# uart-cut.net
KiCad netlist of a schematic drawn in Altium Designer
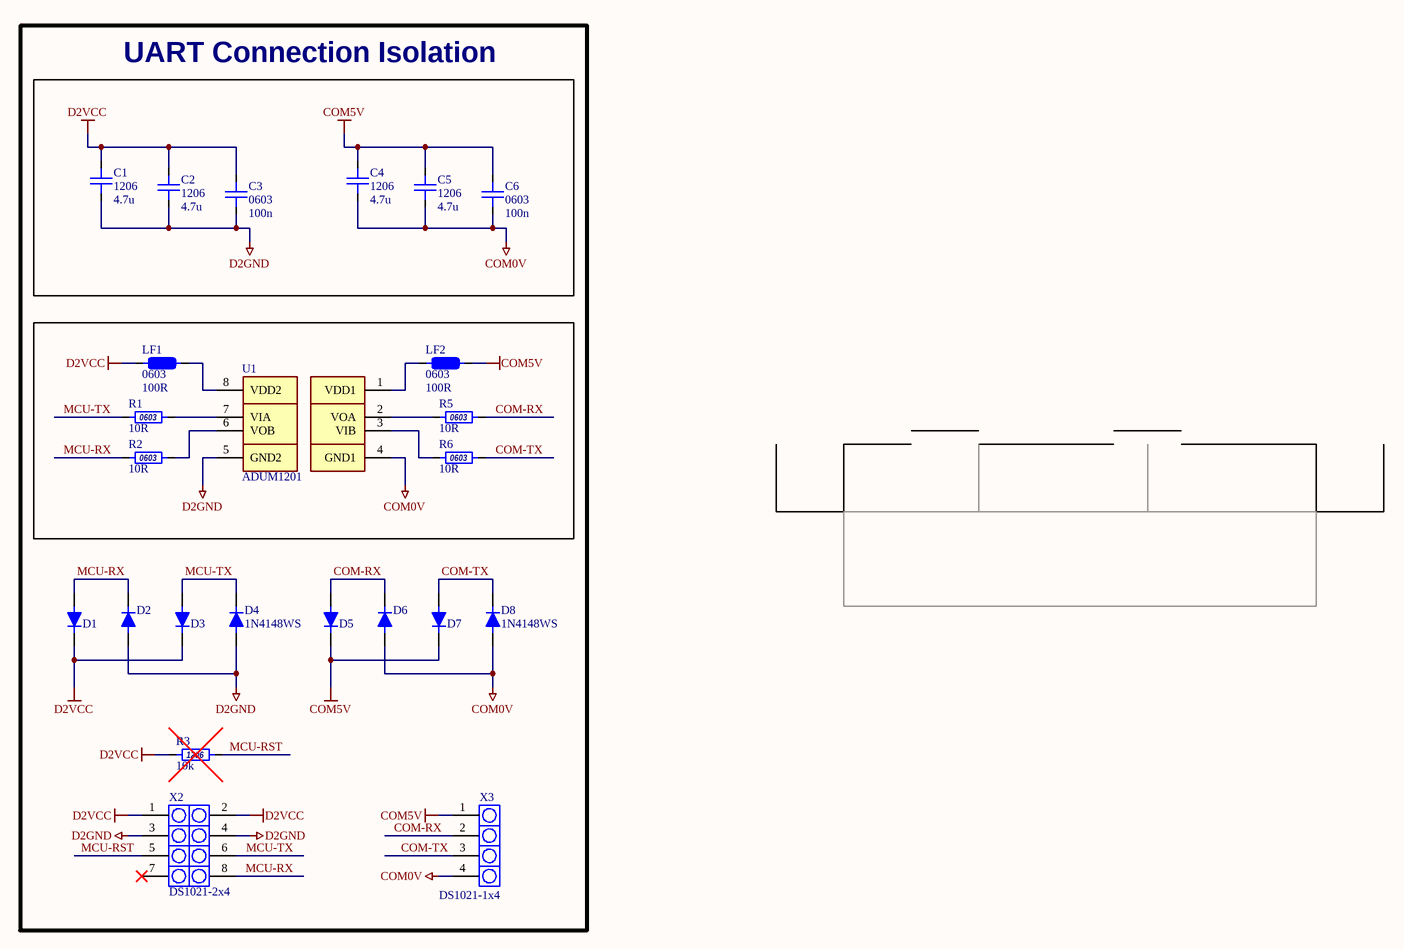
[diagram p0: uart-cut.SchDoc]

(export (version "E")
  (design (tool "Eeschema 10.0.6"))
  (components
    (comp (ref "C1")
      (value "4.7u")
      (footprint "CAP1206P")
      (description "C1206 10% 25V")
      (fields
        (field (name "TOLERANCE") "10%")
        (field (name "PACKAGE") "1206")
        (field (name "MANUFACTURER") "Yageo")
      )
      (libsource (lib "rlc-capacitor") (part "C1206"))
    )
    (comp (ref "C2")
      (value "4.7u")
      (footprint "CAP1206P")
      (description "C1206 10% 25V")
      (fields
        (field (name "TOLERANCE") "10%")
        (field (name "PACKAGE") "1206")
        (field (name "MANUFACTURER") "Yageo")
      )
      (libsource (lib "rlc-capacitor") (part "C1206"))
    )
    (comp (ref "C3")
      (value "100n")
      (footprint "CAP0603P")
      (description "C0603 10% 25V")
      (fields
        (field (name "TOLERANCE") "10%")
        (field (name "PACKAGE") "0603")
        (field (name "MANUFACTURER") "Yageo")
      )
      (libsource (lib "rlc-capacitor") (part "C0603"))
    )
    (comp (ref "C4")
      (value "4.7u")
      (footprint "CAP1206P")
      (description "C1206 10% 25V")
      (fields
        (field (name "TOLERANCE") "10%")
        (field (name "PACKAGE") "1206")
        (field (name "MANUFACTURER") "Yageo")
      )
      (libsource (lib "rlc-capacitor") (part "C1206"))
    )
    (comp (ref "C5")
      (value "4.7u")
      (footprint "CAP1206P")
      (description "C1206 10% 25V")
      (fields
        (field (name "TOLERANCE") "10%")
        (field (name "PACKAGE") "1206")
        (field (name "MANUFACTURER") "Yageo")
      )
      (libsource (lib "rlc-capacitor") (part "C1206"))
    )
    (comp (ref "C6")
      (value "100n")
      (footprint "CAP0603P")
      (description "C0603 10% 25V")
      (fields
        (field (name "TOLERANCE") "10%")
        (field (name "PACKAGE") "0603")
        (field (name "MANUFACTURER") "Yageo")
      )
      (libsource (lib "rlc-capacitor") (part "C0603"))
    )
    (comp (ref "D1")
      (value "1N4148WS")
      (footprint "DIOD-SOD323-2-A_V")
      (description "Fast Switching Diode, 75 V, 0.3 A, -65 to 150 degC, 2-Pin SOD323, RoHS, Tape and Reel")
      (fields (field (name "MANUFACTURER") "Diodes") (field (name "MANUFACTURERPARTNUMBER") "1N4148WS-7-F"))
      (libsource (lib "power-diode") (part "1N4148WS"))
    )
    (comp (ref "D2")
      (value "1N4148WS")
      (footprint "DIOD-SOD323-2-A_V")
      (description "Fast Switching Diode, 75 V, 0.3 A, -65 to 150 degC, 2-Pin SOD323, RoHS, Tape and Reel")
      (fields (field (name "MANUFACTURER") "Diodes") (field (name "MANUFACTURERPARTNUMBER") "1N4148WS-7-F"))
      (libsource (lib "power-diode") (part "1N4148WS"))
    )
    (comp (ref "D3")
      (value "1N4148WS")
      (footprint "DIOD-SOD323-2-A_V")
      (description "Fast Switching Diode, 75 V, 0.3 A, -65 to 150 degC, 2-Pin SOD323, RoHS, Tape and Reel")
      (fields (field (name "MANUFACTURER") "Diodes") (field (name "MANUFACTURERPARTNUMBER") "1N4148WS-7-F"))
      (libsource (lib "power-diode") (part "1N4148WS"))
    )
    (comp (ref "D4")
      (value "1N4148WS")
      (footprint "DIOD-SOD323-2-A_V")
      (description "Fast Switching Diode, 75 V, 0.3 A, -65 to 150 degC, 2-Pin SOD323, RoHS, Tape and Reel")
      (fields (field (name "MANUFACTURER") "Diodes") (field (name "MANUFACTURERPARTNUMBER") "1N4148WS-7-F"))
      (libsource (lib "power-diode") (part "1N4148WS"))
    )
    (comp (ref "D5")
      (value "1N4148WS")
      (footprint "DIOD-SOD323-2-A_V")
      (description "Fast Switching Diode, 75 V, 0.3 A, -65 to 150 degC, 2-Pin SOD323, RoHS, Tape and Reel")
      (fields (field (name "MANUFACTURER") "Diodes") (field (name "MANUFACTURERPARTNUMBER") "1N4148WS-7-F"))
      (libsource (lib "power-diode") (part "1N4148WS"))
    )
    (comp (ref "D6")
      (value "1N4148WS")
      (footprint "DIOD-SOD323-2-A_V")
      (description "Fast Switching Diode, 75 V, 0.3 A, -65 to 150 degC, 2-Pin SOD323, RoHS, Tape and Reel")
      (fields (field (name "MANUFACTURER") "Diodes") (field (name "MANUFACTURERPARTNUMBER") "1N4148WS-7-F"))
      (libsource (lib "power-diode") (part "1N4148WS"))
    )
    (comp (ref "D7")
      (value "1N4148WS")
      (footprint "DIOD-SOD323-2-A_V")
      (description "Fast Switching Diode, 75 V, 0.3 A, -65 to 150 degC, 2-Pin SOD323, RoHS, Tape and Reel")
      (fields (field (name "MANUFACTURER") "Diodes") (field (name "MANUFACTURERPARTNUMBER") "1N4148WS-7-F"))
      (libsource (lib "power-diode") (part "1N4148WS"))
    )
    (comp (ref "D8")
      (value "1N4148WS")
      (footprint "DIOD-SOD323-2-A_V")
      (description "Fast Switching Diode, 75 V, 0.3 A, -65 to 150 degC, 2-Pin SOD323, RoHS, Tape and Reel")
      (fields (field (name "MANUFACTURER") "Diodes") (field (name "MANUFACTURERPARTNUMBER") "1N4148WS-7-F"))
      (libsource (lib "power-diode") (part "1N4148WS"))
    )
    (comp (ref "LF1")
      (value "100R")
      (footprint "IND0603")
      (description "BEAD0603 25% 100R @100MHz 2.0A 45mR")
      (fields
        (field (name "TOLERANCE") "25%")
        (field (name "PACKAGE") "0603")
        (field (name "MANUFACTURER") "Murata Electronics")
      )
      (libsource (lib "rlc-inductor") (part "FB0603"))
    )
    (comp (ref "LF2")
      (value "100R")
      (footprint "IND0603")
      (description "BEAD0603 25% 100R @100MHz 2.0A 45mR")
      (fields
        (field (name "TOLERANCE") "25%")
        (field (name "PACKAGE") "0603")
        (field (name "MANUFACTURER") "Murata Electronics")
      )
      (libsource (lib "rlc-inductor") (part "FB0603"))
    )
    (comp (ref "R1")
      (value "10R")
      (footprint "RES0603")
      (description "R0603 5%")
      (fields (field (name "TOLERANCE") "5%") (field (name "MANUFACTURER") "Yageo"))
      (libsource (lib "rlc-resistor") (part "R0603"))
    )
    (comp (ref "R2")
      (value "10R")
      (footprint "RES0603")
      (description "R0603 5%")
      (fields (field (name "TOLERANCE") "5%") (field (name "MANUFACTURER") "Yageo"))
      (libsource (lib "rlc-resistor") (part "R0603"))
    )
    (comp (ref "R3")
      (value "10k")
      (footprint "RES1206")
      (description "R1206 5%")
      (fields (field (name "TOLERANCE") "1%") (field (name "MANUFACTURER") "Yageo"))
      (libsource (lib "rlc-resistor") (part "R1206"))
    )
    (comp (ref "R5")
      (value "10R")
      (footprint "RES0603")
      (description "R0603 5%")
      (fields (field (name "TOLERANCE") "5%") (field (name "MANUFACTURER") "Yageo"))
      (libsource (lib "rlc-resistor") (part "R0603"))
    )
    (comp (ref "R6")
      (value "10R")
      (footprint "RES0603")
      (description "R0603 5%")
      (fields (field (name "TOLERANCE") "5%") (field (name "MANUFACTURER") "Yageo"))
      (libsource (lib "rlc-resistor") (part "R0603"))
    )
    (comp (ref "U1")
      (value "ADUM1201")
      (footprint "SOIC-8")
      (description "RX/TX Isolation 5V 1MHz")
      (fields
        (field (name "MANUFACTURER") "Analog Devices")
        (field (name "MANUFACTURERPARTNUMBER") "ADUM1201ARZ")
        (field (name "NAME") "ADUM1201")
      )
      (libsource (lib "ic-isolation") (part "ADUM1201"))
    )
    (comp (ref "X2")
      (value "DS1021-2x4")
      (footprint "PLS-2X4")
      (description "Pinout 2x2")
      (fields (field (name "MANUFACTURER") "Connfly"))
      (libsource (lib "mech-connector") (part "PLS 2x4"))
    )
    (comp (ref "X3")
      (value "DS1021-1x4")
      (footprint "PLS-1X4")
      (description "Standard PLS pinout")
      (fields (field (name "MANUFACTURER") "Connfly"))
      (libsource (lib "mech-connector") (part "PLS 1x4"))
    )
  )
  (nets
    (net (code "1") (name "/COM-RX") (class "Default")
      (node (ref "D5") (pin "1") (pinfunction "A_1") (pintype "passive"))
      (node (ref "D6") (pin "2") (pinfunction "K_2") (pintype "passive"))
      (node (ref "R5") (pin "2") (pinfunction "2_2") (pintype "passive"))
      (node (ref "X3") (pin "2") (pinfunction "2_2") (pintype "passive"))
    )
    (net (code "2") (name "/COM-TX") (class "Default")
      (node (ref "D7") (pin "1") (pinfunction "A_1") (pintype "passive"))
      (node (ref "D8") (pin "2") (pinfunction "K_2") (pintype "passive"))
      (node (ref "R6") (pin "2") (pinfunction "2_2") (pintype "passive"))
      (node (ref "X3") (pin "3") (pinfunction "3_3") (pintype "passive"))
    )
    (net (code "3") (name "/MCU-RST") (class "Default")
      (node (ref "R3") (pin "2") (pinfunction "2_2") (pintype "passive"))
      (node (ref "X2") (pin "5") (pinfunction "5_5") (pintype "passive"))
    )
    (net (code "4") (name "/MCU-RX") (class "Default")
      (node (ref "D1") (pin "1") (pinfunction "A_1") (pintype "passive"))
      (node (ref "D2") (pin "2") (pinfunction "K_2") (pintype "passive"))
      (node (ref "R2") (pin "1") (pinfunction "1_1") (pintype "passive"))
      (node (ref "X2") (pin "8") (pinfunction "8_8") (pintype "passive"))
    )
    (net (code "5") (name "/MCU-TX") (class "Default")
      (node (ref "D3") (pin "1") (pinfunction "A_1") (pintype "passive"))
      (node (ref "D4") (pin "2") (pinfunction "K_2") (pintype "passive"))
      (node (ref "R1") (pin "1") (pinfunction "1_1") (pintype "passive"))
      (node (ref "X2") (pin "6") (pinfunction "6_6") (pintype "passive"))
    )
    (net (code "6") (name "COM0V") (class "Default")
      (node (ref "C4") (pin "1") (pinfunction "1_1") (pintype "passive"))
      (node (ref "C5") (pin "1") (pinfunction "1_1") (pintype "passive"))
      (node (ref "C6") (pin "1") (pinfunction "1_1") (pintype "passive"))
      (node (ref "D6") (pin "1") (pinfunction "A_1") (pintype "passive"))
      (node (ref "D8") (pin "1") (pinfunction "A_1") (pintype "passive"))
      (node (ref "U1") (pin "4") (pinfunction "GND1_4") (pintype "passive"))
      (node (ref "X3") (pin "4") (pinfunction "4_4") (pintype "passive"))
    )
    (net (code "7") (name "COM5V") (class "Default")
      (node (ref "C4") (pin "2") (pinfunction "2_2") (pintype "passive"))
      (node (ref "C5") (pin "2") (pinfunction "2_2") (pintype "passive"))
      (node (ref "C6") (pin "2") (pinfunction "2_2") (pintype "passive"))
      (node (ref "D5") (pin "2") (pinfunction "K_2") (pintype "passive"))
      (node (ref "D7") (pin "2") (pinfunction "K_2") (pintype "passive"))
      (node (ref "LF2") (pin "1") (pinfunction "1_1") (pintype "passive"))
      (node (ref "X3") (pin "1") (pinfunction "1_1") (pintype "passive"))
    )
    (net (code "8") (name "D2GND") (class "Default")
      (node (ref "C1") (pin "1") (pinfunction "1_1") (pintype "passive"))
      (node (ref "C2") (pin "1") (pinfunction "1_1") (pintype "passive"))
      (node (ref "C3") (pin "1") (pinfunction "1_1") (pintype "passive"))
      (node (ref "D2") (pin "1") (pinfunction "A_1") (pintype "passive"))
      (node (ref "D4") (pin "1") (pinfunction "A_1") (pintype "passive"))
      (node (ref "U1") (pin "5") (pinfunction "GND2_5") (pintype "passive"))
      (node (ref "X2") (pin "3") (pinfunction "3_3") (pintype "passive"))
      (node (ref "X2") (pin "4") (pinfunction "4_4") (pintype "passive"))
    )
    (net (code "9") (name "D2VCC") (class "Default")
      (node (ref "C1") (pin "2") (pinfunction "2_2") (pintype "passive"))
      (node (ref "C2") (pin "2") (pinfunction "2_2") (pintype "passive"))
      (node (ref "C3") (pin "2") (pinfunction "2_2") (pintype "passive"))
      (node (ref "D1") (pin "2") (pinfunction "K_2") (pintype "passive"))
      (node (ref "D3") (pin "2") (pinfunction "K_2") (pintype "passive"))
      (node (ref "LF1") (pin "1") (pinfunction "1_1") (pintype "passive"))
      (node (ref "R3") (pin "1") (pinfunction "1_1") (pintype "passive"))
      (node (ref "X2") (pin "1") (pinfunction "1_1") (pintype "passive"))
      (node (ref "X2") (pin "2") (pinfunction "2_2") (pintype "passive"))
    )
    (net (code "10") (name "Net-(U1-VDD1)") (class "Default")
      (node (ref "LF2") (pin "2") (pinfunction "2_2") (pintype "passive"))
      (node (ref "U1") (pin "1") (pinfunction "VDD1_1") (pintype "passive"))
    )
    (net (code "11") (name "Net-(U1-VDD2)") (class "Default")
      (node (ref "LF1") (pin "2") (pinfunction "2_2") (pintype "passive"))
      (node (ref "U1") (pin "8") (pinfunction "VDD2_8") (pintype "passive"))
    )
    (net (code "12") (name "Net-(U1-VIA)") (class "Default")
      (node (ref "R1") (pin "2") (pinfunction "2_2") (pintype "passive"))
      (node (ref "U1") (pin "7") (pinfunction "VIA_7") (pintype "passive"))
    )
    (net (code "13") (name "Net-(U1-VIB)") (class "Default")
      (node (ref "R6") (pin "1") (pinfunction "1_1") (pintype "passive"))
      (node (ref "U1") (pin "3") (pinfunction "VIB_3") (pintype "passive"))
    )
    (net (code "14") (name "Net-(U1-VOA)") (class "Default")
      (node (ref "R5") (pin "1") (pinfunction "1_1") (pintype "passive"))
      (node (ref "U1") (pin "2") (pinfunction "VOA_2") (pintype "passive"))
    )
    (net (code "15") (name "Net-(U1-VOB)") (class "Default")
      (node (ref "R2") (pin "2") (pinfunction "2_2") (pintype "passive"))
      (node (ref "U1") (pin "6") (pinfunction "VOB_6") (pintype "passive"))
    )
    (net (code "16") (name "unconnected-(X2-Pad7)") (class "Default")
      (node (ref "X2") (pin "7") (pinfunction "7_7") (pintype "passive+no_connect"))
    )
  )
)
